# YosanoLoveButton.net
KiCad netlist of a schematic drawn in EAGLE
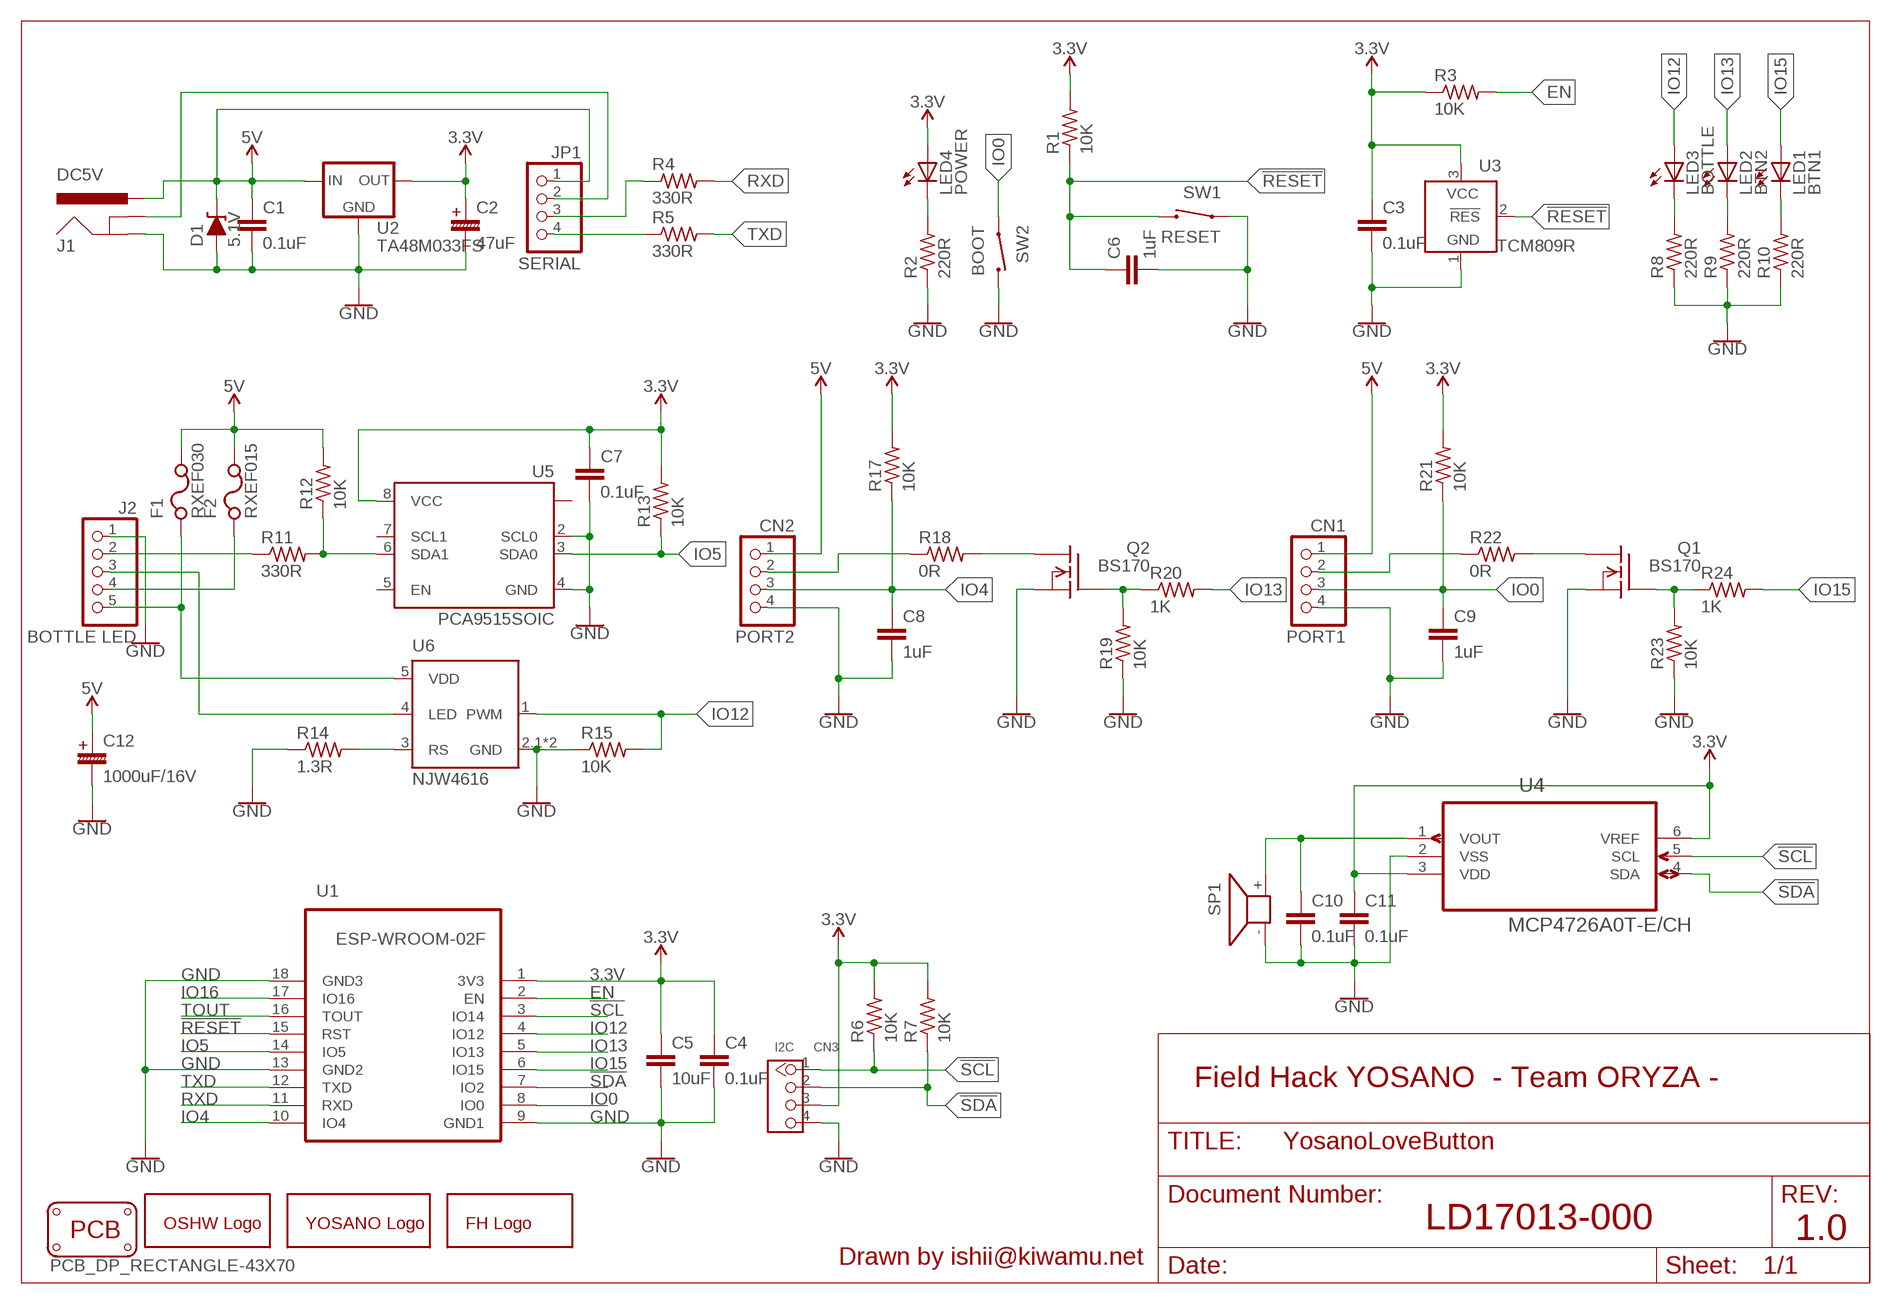
[diagram p0: schematic, sheet 1]

(export (version "E")
  (design (tool "Eeschema 10.0.6"))
  (components
    (comp (ref "C1")
      (value "0.1uF")
      (footprint "eagle-import:C5B2.5")
      (libsource (lib "eagle-import") (part "capacitor-wima_C5/2.5"))
    )
    (comp (ref "C2")
      (value "47uF")
      (footprint "eagle-import:E2,0-5")
      (libsource (lib "eagle-import") (part "C-PR-2,0X5"))
    )
    (comp (ref "C3")
      (value "0.1uF")
      (footprint "eagle-import:C5B2.5")
      (libsource (lib "eagle-import") (part "capacitor-wima_C5/2.5"))
    )
    (comp (ref "C4")
      (value "0.1uF")
      (footprint "eagle-import:C5B2.5")
      (libsource (lib "eagle-import") (part "capacitor-wima_C5/2.5"))
    )
    (comp (ref "C5")
      (value "10uF")
      (footprint "eagle-import:C5B2.5")
      (libsource (lib "eagle-import") (part "capacitor-wima_C5/2.5"))
    )
    (comp (ref "C6")
      (value "1uF")
      (footprint "eagle-import:C5B2.5")
      (libsource (lib "eagle-import") (part "capacitor-wima_C5/2.5"))
    )
    (comp (ref "C7")
      (value "0.1uF")
      (footprint "eagle-import:C5B2.5")
      (libsource (lib "eagle-import") (part "capacitor-wima_C5/2.5"))
    )
    (comp (ref "C8")
      (value "1uF")
      (footprint "eagle-import:C5B2.5")
      (libsource (lib "eagle-import") (part "capacitor-wima_C5/2.5"))
    )
    (comp (ref "C9")
      (value "1uF")
      (footprint "eagle-import:C5B2.5")
      (libsource (lib "eagle-import") (part "capacitor-wima_C5/2.5"))
    )
    (comp (ref "C10")
      (value "0.1uF")
      (footprint "eagle-import:C5B2.5")
      (fields (field (name "MF") "株式会社村田製作所(muRata)") (field (name "MPN") "RDER72E104K2K1H03B"))
      (libsource (lib "eagle-import") (part "C5/2.5"))
    )
    (comp (ref "C11")
      (value "0.1uF")
      (footprint "eagle-import:C5B2.5")
      (fields (field (name "MF") "株式会社村田製作所(muRata)") (field (name "MPN") "RDER72E104K2K1H03B"))
      (libsource (lib "eagle-import") (part "C5/2.5"))
    )
    (comp (ref "C12")
      (value "1000uF/16V")
      (footprint "eagle-import:E5,0-10")
      (libsource (lib "eagle-import") (part "C-PR-5,0X10"))
    )
    (comp (ref "CN1")
      (value "PORT1")
      (footprint "eagle-import:B4B-XH")
      (libsource (lib "eagle-import") (part "04-JST-XH-B4B-XH-A"))
    )
    (comp (ref "CN2")
      (value "PORT2")
      (footprint "eagle-import:B4B-XH")
      (libsource (lib "eagle-import") (part "04-JST-XH-B4B-XH-A"))
    )
    (comp (ref "CN3")
      (value "I2C")
      (footprint "eagle-import:HW4-2.0")
      (libsource (lib "eagle-import") (part "GROVE-CONNECTOR-DIP(4P-2.0)"))
    )
    (comp (ref "D1")
      (value "5.1V")
      (footprint "eagle-import:ZDIO-5-LD")
      (libsource (lib "eagle-import") (part "ZENER-DIODEZD-5LD"))
    )
    (comp (ref "F1")
      (value "RXEF030")
      (footprint "eagle-import:PTC-PTH")
      (libsource (lib "eagle-import") (part "PTCPTH"))
    )
    (comp (ref "F2")
      (value "RXEF015")
      (footprint "eagle-import:PTC-PTH")
      (libsource (lib "eagle-import") (part "PTCPTH"))
    )
    (comp (ref "GOLD_ORB_SM1")
      (value "OSHWLOGOLOGO5MM")
      (footprint "eagle-import:OSHW_5MM")
      (libsource (lib "eagle-import") (part "OSHWLOGOLOGO5MM"))
    )
    (comp (ref "J1")
      (value "DC5V")
      (footprint "eagle-import:POWER_JACK_PTH")
      (libsource (lib "eagle-import") (part "POWER_JACK"))
    )
    (comp (ref "J2")
      (value "BOTTLE LED")
      (footprint "eagle-import:MD-50SM")
      (fields (field (name "MF") "CUI") (field (name "MPN") "MD-50SM"))
      (libsource (lib "eagle-import") (part "MINIDIN-5P"))
    )
    (comp (ref "JP1")
      (value "SERIAL")
      (footprint "eagle-import:1X04")
      (libsource (lib "eagle-import") (part "PINHD-1X4"))
    )
    (comp (ref "LED1")
      (value "BTN1")
      (footprint "eagle-import:LED3MM")
      (libsource (lib "eagle-import") (part "LED3MM"))
    )
    (comp (ref "LED2")
      (value "BTN2")
      (footprint "eagle-import:LED3MM")
      (libsource (lib "eagle-import") (part "LED3MM"))
    )
    (comp (ref "LED3")
      (value "BOTTLE")
      (footprint "eagle-import:LED3MM")
      (libsource (lib "eagle-import") (part "LED3MM"))
    )
    (comp (ref "LED4")
      (value "POWER")
      (footprint "eagle-import:LED3MM")
      (libsource (lib "eagle-import") (part "LED3MM"))
    )
    (comp (ref "PCB1")
      (value "PCB_DP_RECTANGLE-43X70")
      (footprint "eagle-import:DP7043_V1")
      (libsource (lib "eagle-import") (part "PCB_DP_RECTANGLE-43X70"))
    )
    (comp (ref "Q1")
      (value "BS170")
      (footprint "eagle-import:TO92")
      (fields (field (name "MF") "FAIRCHILD"))
      (libsource (lib "eagle-import") (part "BS170"))
    )
    (comp (ref "Q2")
      (value "BS170")
      (footprint "eagle-import:TO92")
      (fields (field (name "MF") "FAIRCHILD"))
      (libsource (lib "eagle-import") (part "BS170"))
    )
    (comp (ref "R1")
      (value "10K")
      (footprint "eagle-import:0204_5")
      (libsource (lib "eagle-import") (part "R-US_0204/5"))
    )
    (comp (ref "R2")
      (value "220R")
      (footprint "eagle-import:0204_5")
      (libsource (lib "eagle-import") (part "R-US_0204/5"))
    )
    (comp (ref "R3")
      (value "10K")
      (footprint "eagle-import:0204_5")
      (libsource (lib "eagle-import") (part "R-US_0204/5"))
    )
    (comp (ref "R4")
      (value "330R")
      (footprint "eagle-import:0204_5")
      (libsource (lib "eagle-import") (part "R-US_0204/5"))
    )
    (comp (ref "R5")
      (value "330R")
      (footprint "eagle-import:0204_5")
      (libsource (lib "eagle-import") (part "R-US_0204/5"))
    )
    (comp (ref "R6")
      (value "10K")
      (footprint "eagle-import:0204_5")
      (libsource (lib "eagle-import") (part "R-US_0204/5"))
    )
    (comp (ref "R7")
      (value "10K")
      (footprint "eagle-import:0204_5")
      (libsource (lib "eagle-import") (part "R-US_0204/5"))
    )
    (comp (ref "R8")
      (value "220R")
      (footprint "eagle-import:0204_5")
      (libsource (lib "eagle-import") (part "R-US_0204/5"))
    )
    (comp (ref "R9")
      (value "220R")
      (footprint "eagle-import:0204_5")
      (libsource (lib "eagle-import") (part "R-US_0204/5"))
    )
    (comp (ref "R10")
      (value "220R")
      (footprint "eagle-import:0204_5")
      (libsource (lib "eagle-import") (part "R-US_0204/5"))
    )
    (comp (ref "R11")
      (value "330R")
      (footprint "eagle-import:0204_5")
      (libsource (lib "eagle-import") (part "R-US_0204/5"))
    )
    (comp (ref "R12")
      (value "10K")
      (footprint "eagle-import:0204_5")
      (libsource (lib "eagle-import") (part "R-US_0204/5"))
    )
    (comp (ref "R13")
      (value "10K")
      (footprint "eagle-import:0204_5")
      (libsource (lib "eagle-import") (part "R-US_0204/5"))
    )
    (comp (ref "R14")
      (value "1.3R")
      (footprint "eagle-import:0204_5")
      (libsource (lib "eagle-import") (part "R-US_0204/5"))
    )
    (comp (ref "R15")
      (value "10K")
      (footprint "eagle-import:0204_5")
      (libsource (lib "eagle-import") (part "R-US_0204/5"))
    )
    (comp (ref "R17")
      (value "10K")
      (footprint "eagle-import:0204_5")
      (libsource (lib "eagle-import") (part "R-US_0204/5"))
    )
    (comp (ref "R18")
      (value "0R")
      (footprint "eagle-import:0204_5")
      (libsource (lib "eagle-import") (part "R-US_0204/5"))
    )
    (comp (ref "R19")
      (value "10K")
      (footprint "eagle-import:0204_5")
      (libsource (lib "eagle-import") (part "R-US_0204/5"))
    )
    (comp (ref "R20")
      (value "1K")
      (footprint "eagle-import:0204_5")
      (libsource (lib "eagle-import") (part "R-US_0204/5"))
    )
    (comp (ref "R21")
      (value "10K")
      (footprint "eagle-import:0204_5")
      (libsource (lib "eagle-import") (part "R-US_0204/5"))
    )
    (comp (ref "R22")
      (value "0R")
      (footprint "eagle-import:0204_5")
      (libsource (lib "eagle-import") (part "R-US_0204/5"))
    )
    (comp (ref "R23")
      (value "10K")
      (footprint "eagle-import:0204_5")
      (libsource (lib "eagle-import") (part "R-US_0204/5"))
    )
    (comp (ref "R24")
      (value "1K")
      (footprint "eagle-import:0204_5")
      (libsource (lib "eagle-import") (part "R-US_0204/5"))
    )
    (comp (ref "SP1")
      (value "PKM13EPYH4000")
      (footprint "eagle-import:PKM13EPYH4000")
      (fields (field (name "MF") "muRata"))
      (libsource (lib "eagle-import") (part "PKM13EPYH4000"))
    )
    (comp (ref "SW1")
      (value "RESET")
      (footprint "eagle-import:TVBP06")
      (libsource (lib "eagle-import") (part "TVBP06"))
    )
    (comp (ref "SW2")
      (value "BOOT")
      (footprint "eagle-import:TVBP06")
      (libsource (lib "eagle-import") (part "TVBP06"))
    )
    (comp (ref "U$1")
      (value "YOSANOLOGO")
      (footprint "eagle-import:YOSANOCHO")
      (libsource (lib "eagle-import") (part "YOSANOLOGO"))
    )
    (comp (ref "U$2")
      (value "FHLOGO")
      (footprint "eagle-import:FIELDHACK-YOSANO")
      (libsource (lib "eagle-import") (part "FHLOGO"))
    )
    (comp (ref "U1")
      (value "ESP-WROOM-02F")
      (footprint "eagle-import:FRONT-FACE")
      (fields (field (name "MF") "Espressif") (field (name "MPN") "ESP-WROOM-02"))
      (libsource (lib "eagle-import") (part "ESP-WROOM-02F"))
    )
    (comp (ref "U2")
      (value "TA48M033FS")
      (footprint "eagle-import:HSIP3")
      (fields (field (name "MF") "株式会社東芝セミコンダクター社(TOSHIBA)") (field (name "MPN") "TA48M033F(S Q)"))
      (libsource (lib "eagle-import") (part "TA48MS033F"))
    )
    (comp (ref "U3")
      (value "TCM809R")
      (footprint "eagle-import:SOT23B-3")
      (fields (field (name "MF") "MICROCHIP") (field (name "MPN") "TCM809MENB713"))
      (libsource (lib "eagle-import") (part "TCM809"))
    )
    (comp (ref "U4")
      (value "MCP4726A0T-E/CH")
      (footprint "eagle-import:SOT95P270X145-6N")
      (fields (field (name "MF") "Microchip") (field (name "MPN") "MCP4725A0T-E/CH"))
      (libsource (lib "eagle-import") (part "MCP4726A0T-E/CH"))
    )
    (comp (ref "U5")
      (value "PCA9515SOIC")
      (footprint "eagle-import:SO08")
      (libsource (lib "eagle-import") (part "PCA9515SOIC"))
    )
    (comp (ref "U6")
      (value "NJW4616")
      (footprint "eagle-import:SOT-89-5")
      (libsource (lib "eagle-import") (part "NJW4616"))
    )
  )
  (nets
    (net (code "1") (name "/IO16") (class "Default")
      (node (ref "U1") (pin "17") (pinfunction "IO16_17") (pintype "bidirectional"))
    )
    (net (code "2") (name "/TOUT") (class "Default")
      (node (ref "U1") (pin "16") (pinfunction "TOUT_16") (pintype "bidirectional"))
    )
    (net (code "3") (name "/~{RESET}") (class "Default")
      (node (ref "C6") (pin "1") (pinfunction "1_1") (pintype "passive"))
      (node (ref "R1") (pin "1") (pinfunction "1_1") (pintype "passive"))
      (node (ref "SW1") (pin "2") (pinfunction "2_2") (pintype "passive"))
      (node (ref "U1") (pin "15") (pinfunction "RST_15") (pintype "bidirectional"))
      (node (ref "U3") (pin "2") (pinfunction "~{RES}_2") (pintype "output"))
    )
    (net (code "4") (name "/~{SCL}") (class "Default")
      (node (ref "CN3") (pin "1") (pinfunction "1_1") (pintype "bidirectional"))
      (node (ref "R6") (pin "1") (pinfunction "1_1") (pintype "passive"))
      (node (ref "U1") (pin "3") (pinfunction "IO14_3") (pintype "bidirectional"))
      (node (ref "U4") (pin "5") (pinfunction "SCL_5") (pintype "input"))
    )
    (net (code "5") (name "/~{SDA}") (class "Default")
      (node (ref "CN3") (pin "2") (pinfunction "2_2") (pintype "bidirectional"))
      (node (ref "R7") (pin "1") (pinfunction "1_1") (pintype "passive"))
      (node (ref "U1") (pin "7") (pinfunction "IO2_7") (pintype "bidirectional"))
      (node (ref "U4") (pin "4") (pinfunction "SDA_4") (pintype "bidirectional"))
    )
    (net (code "6") (name "3.3V") (class "Default")
      (node (ref "C11") (pin "1") (pinfunction "1_1") (pintype "passive"))
      (node (ref "C2") (pin "+") (pinfunction "+_+") (pintype "passive"))
      (node (ref "C3") (pin "1") (pinfunction "1_1") (pintype "passive"))
      (node (ref "C4") (pin "1") (pinfunction "1_1") (pintype "passive"))
      (node (ref "C5") (pin "1") (pinfunction "1_1") (pintype "passive"))
      (node (ref "C7") (pin "1") (pinfunction "1_1") (pintype "passive"))
      (node (ref "CN3") (pin "3") (pinfunction "3_3") (pintype "bidirectional"))
      (node (ref "LED4") (pin "A") (pinfunction "A_A") (pintype "passive"))
      (node (ref "R1") (pin "2") (pinfunction "2_2") (pintype "passive"))
      (node (ref "R13") (pin "2") (pinfunction "2_2") (pintype "passive"))
      (node (ref "R17") (pin "2") (pinfunction "2_2") (pintype "passive"))
      (node (ref "R21") (pin "2") (pinfunction "2_2") (pintype "passive"))
      (node (ref "R3") (pin "1") (pinfunction "1_1") (pintype "passive"))
      (node (ref "R6") (pin "2") (pinfunction "2_2") (pintype "passive"))
      (node (ref "R7") (pin "2") (pinfunction "2_2") (pintype "passive"))
      (node (ref "U1") (pin "1") (pinfunction "3V3_1") (pintype "power_in"))
      (node (ref "U2") (pin "P$2") (pinfunction "OUT_P$2") (pintype "passive"))
      (node (ref "U3") (pin "3") (pinfunction "VCC_3") (pintype "power_in"))
      (node (ref "U4") (pin "3") (pinfunction "VDD_3") (pintype "power_in"))
      (node (ref "U4") (pin "6") (pinfunction "VREF_6") (pintype "power_in"))
      (node (ref "U5") (pin "8") (pinfunction "VCC_8") (pintype "power_in"))
    )
    (net (code "7") (name "5V") (class "Default")
      (node (ref "C1") (pin "1") (pinfunction "1_1") (pintype "passive"))
      (node (ref "C12") (pin "+") (pinfunction "+_+") (pintype "passive"))
      (node (ref "CN1") (pin "1") (pinfunction "1_1") (pintype "passive"))
      (node (ref "CN2") (pin "1") (pinfunction "1_1") (pintype "passive"))
      (node (ref "D1") (pin "C") (pinfunction "C_C") (pintype "passive"))
      (node (ref "F1") (pin "2") (pinfunction "2_2") (pintype "bidirectional"))
      (node (ref "F2") (pin "2") (pinfunction "2_2") (pintype "bidirectional"))
      (node (ref "J1") (pin "PWR") (pinfunction "PWR_PWR") (pintype "bidirectional"))
      (node (ref "JP1") (pin "1") (pinfunction "1_1") (pintype "passive"))
      (node (ref "R12") (pin "2") (pinfunction "2_2") (pintype "passive"))
      (node (ref "U2") (pin "P$1") (pinfunction "IN_P$1") (pintype "input"))
    )
    (net (code "8") (name "EN") (class "Default")
      (node (ref "R3") (pin "2") (pinfunction "2_2") (pintype "passive"))
      (node (ref "U1") (pin "2") (pinfunction "EN_2") (pintype "bidirectional"))
    )
    (net (code "9") (name "GND") (class "Default")
      (node (ref "C1") (pin "2") (pinfunction "2_2") (pintype "passive"))
      (node (ref "C10") (pin "2") (pinfunction "2_2") (pintype "passive"))
      (node (ref "C11") (pin "2") (pinfunction "2_2") (pintype "passive"))
      (node (ref "C12") (pin "-") (pinfunction "-_-") (pintype "passive"))
      (node (ref "C2") (pin "-") (pinfunction "-_-") (pintype "passive"))
      (node (ref "C3") (pin "2") (pinfunction "2_2") (pintype "passive"))
      (node (ref "C4") (pin "2") (pinfunction "2_2") (pintype "passive"))
      (node (ref "C5") (pin "2") (pinfunction "2_2") (pintype "passive"))
      (node (ref "C6") (pin "2") (pinfunction "2_2") (pintype "passive"))
      (node (ref "C7") (pin "2") (pinfunction "2_2") (pintype "passive"))
      (node (ref "C8") (pin "2") (pinfunction "2_2") (pintype "passive"))
      (node (ref "C9") (pin "2") (pinfunction "2_2") (pintype "passive"))
      (node (ref "CN1") (pin "4") (pinfunction "4_4") (pintype "passive"))
      (node (ref "CN2") (pin "4") (pinfunction "4_4") (pintype "passive"))
      (node (ref "CN3") (pin "4") (pinfunction "4_4") (pintype "bidirectional"))
      (node (ref "D1") (pin "A") (pinfunction "A_A") (pintype "passive"))
      (node (ref "J1") (pin "GND") (pinfunction "GND_GND") (pintype "bidirectional"))
      (node (ref "J2") (pin "1") (pinfunction "1_1") (pintype "passive"))
      (node (ref "Q1") (pin "1") (pinfunction "S_1") (pintype "passive"))
      (node (ref "Q2") (pin "1") (pinfunction "S_1") (pintype "passive"))
      (node (ref "R10") (pin "1") (pinfunction "1_1") (pintype "passive"))
      (node (ref "R14") (pin "1") (pinfunction "1_1") (pintype "passive"))
      (node (ref "R15") (pin "1") (pinfunction "1_1") (pintype "passive"))
      (node (ref "R19") (pin "1") (pinfunction "1_1") (pintype "passive"))
      (node (ref "R2") (pin "1") (pinfunction "1_1") (pintype "passive"))
      (node (ref "R23") (pin "1") (pinfunction "1_1") (pintype "passive"))
      (node (ref "R8") (pin "1") (pinfunction "1_1") (pintype "passive"))
      (node (ref "R9") (pin "1") (pinfunction "1_1") (pintype "passive"))
      (node (ref "SP1") (pin "-") (pinfunction "2_-") (pintype "passive"))
      (node (ref "SW1") (pin "1") (pinfunction "1_1") (pintype "passive"))
      (node (ref "SW2") (pin "2") (pinfunction "2_2") (pintype "passive"))
      (node (ref "U1") (pin "13") (pinfunction "GND2_13") (pintype "power_in"))
      (node (ref "U1") (pin "18") (pinfunction "GND3_18") (pintype "power_in"))
      (node (ref "U1") (pin "9") (pinfunction "GND1_9") (pintype "power_in"))
      (node (ref "U2") (pin "P$3") (pinfunction "GND_P$3") (pintype "power_in"))
      (node (ref "U3") (pin "1") (pinfunction "GND_1") (pintype "power_in"))
      (node (ref "U4") (pin "2") (pinfunction "VSS_2") (pintype "power_in"))
      (node (ref "U5") (pin "2") (pinfunction "SCL0_2") (pintype "bidirectional"))
      (node (ref "U5") (pin "4") (pinfunction "GND_4") (pintype "power_in"))
      (node (ref "U6") (pin "2.1") (pinfunction "GND_2.1") (pintype "power_in"))
      (node (ref "U6") (pin "2.2") (pinfunction "GND_2.2") (pintype "power_in"))
    )
    (net (code "10") (name "IO0") (class "Default")
      (node (ref "C9") (pin "1") (pinfunction "1_1") (pintype "passive"))
      (node (ref "CN1") (pin "3") (pinfunction "3_3") (pintype "passive"))
      (node (ref "R21") (pin "1") (pinfunction "1_1") (pintype "passive"))
      (node (ref "SW2") (pin "1") (pinfunction "1_1") (pintype "passive"))
      (node (ref "U1") (pin "8") (pinfunction "IO0_8") (pintype "bidirectional"))
    )
    (net (code "11") (name "IO4") (class "Default")
      (node (ref "C8") (pin "1") (pinfunction "1_1") (pintype "passive"))
      (node (ref "CN2") (pin "3") (pinfunction "3_3") (pintype "passive"))
      (node (ref "R17") (pin "1") (pinfunction "1_1") (pintype "passive"))
      (node (ref "U1") (pin "10") (pinfunction "IO4_10") (pintype "bidirectional"))
    )
    (net (code "12") (name "IO5") (class "Default")
      (node (ref "R13") (pin "1") (pinfunction "1_1") (pintype "passive"))
      (node (ref "U1") (pin "14") (pinfunction "IO5_14") (pintype "open_collector"))
      (node (ref "U5") (pin "3") (pinfunction "SDA0_3") (pintype "bidirectional"))
    )
    (net (code "13") (name "IO12") (class "Default")
      (node (ref "LED3") (pin "A") (pinfunction "A_A") (pintype "passive"))
      (node (ref "R15") (pin "2") (pinfunction "2_2") (pintype "passive"))
      (node (ref "U1") (pin "4") (pinfunction "IO12_4") (pintype "bidirectional"))
      (node (ref "U6") (pin "1") (pinfunction "PWM_1") (pintype "input"))
    )
    (net (code "14") (name "IO13") (class "Default")
      (node (ref "LED2") (pin "A") (pinfunction "A_A") (pintype "passive"))
      (node (ref "R20") (pin "2") (pinfunction "2_2") (pintype "passive"))
      (node (ref "U1") (pin "5") (pinfunction "IO13_5") (pintype "bidirectional"))
    )
    (net (code "15") (name "IO15") (class "Default")
      (node (ref "LED1") (pin "A") (pinfunction "A_A") (pintype "passive"))
      (node (ref "R24") (pin "2") (pinfunction "2_2") (pintype "passive"))
      (node (ref "U1") (pin "6") (pinfunction "IO15_6") (pintype "bidirectional"))
    )
    (net (code "16") (name "Net-(CN1-Pad2)") (class "Default")
      (node (ref "CN1") (pin "2") (pinfunction "2_2") (pintype "passive"))
      (node (ref "R22") (pin "1") (pinfunction "1_1") (pintype "passive"))
    )
    (net (code "17") (name "Net-(CN2-Pad2)") (class "Default")
      (node (ref "CN2") (pin "2") (pinfunction "2_2") (pintype "passive"))
      (node (ref "R18") (pin "1") (pinfunction "1_1") (pintype "passive"))
    )
    (net (code "18") (name "Net-(F2-Pad1)") (class "Default")
      (node (ref "F2") (pin "1") (pinfunction "1_1") (pintype "bidirectional"))
      (node (ref "J2") (pin "4") (pinfunction "4_4") (pintype "passive"))
    )
    (net (code "19") (name "Net-(J1-PadGNDBREAK)") (class "Default")
      (node (ref "J1") (pin "GNDBREAK") (pinfunction "GNDBREAK_GNDBREAK") (pintype "bidirectional"))
      (node (ref "JP1") (pin "2") (pinfunction "2_2") (pintype "passive"))
    )
    (net (code "20") (name "Net-(J2-Pad2)") (class "Default")
      (node (ref "J2") (pin "2") (pinfunction "2_2") (pintype "passive"))
      (node (ref "R11") (pin "1") (pinfunction "1_1") (pintype "passive"))
    )
    (net (code "21") (name "Net-(JP1-Pad3)") (class "Default")
      (node (ref "JP1") (pin "3") (pinfunction "3_3") (pintype "passive"))
      (node (ref "R4") (pin "1") (pinfunction "1_1") (pintype "passive"))
    )
    (net (code "22") (name "Net-(JP1-Pad4)") (class "Default")
      (node (ref "JP1") (pin "4") (pinfunction "4_4") (pintype "passive"))
      (node (ref "R5") (pin "1") (pinfunction "1_1") (pintype "passive"))
    )
    (net (code "23") (name "Net-(LED1-C)") (class "Default")
      (node (ref "LED1") (pin "K") (pinfunction "C_K") (pintype "passive"))
      (node (ref "R10") (pin "2") (pinfunction "2_2") (pintype "passive"))
    )
    (net (code "24") (name "Net-(LED2-C)") (class "Default")
      (node (ref "LED2") (pin "K") (pinfunction "C_K") (pintype "passive"))
      (node (ref "R9") (pin "2") (pinfunction "2_2") (pintype "passive"))
    )
    (net (code "25") (name "Net-(LED3-C)") (class "Default")
      (node (ref "LED3") (pin "K") (pinfunction "C_K") (pintype "passive"))
      (node (ref "R8") (pin "2") (pinfunction "2_2") (pintype "passive"))
    )
    (net (code "26") (name "Net-(LED4-C)") (class "Default")
      (node (ref "LED4") (pin "K") (pinfunction "C_K") (pintype "passive"))
      (node (ref "R2") (pin "2") (pinfunction "2_2") (pintype "passive"))
    )
    (net (code "27") (name "Net-(Q1-D)") (class "Default")
      (node (ref "Q1") (pin "3") (pinfunction "D_3") (pintype "passive"))
      (node (ref "R22") (pin "2") (pinfunction "2_2") (pintype "passive"))
    )
    (net (code "28") (name "Net-(Q1-G)") (class "Default")
      (node (ref "Q1") (pin "2") (pinfunction "G_2") (pintype "passive"))
      (node (ref "R23") (pin "2") (pinfunction "2_2") (pintype "passive"))
      (node (ref "R24") (pin "1") (pinfunction "1_1") (pintype "passive"))
    )
    (net (code "29") (name "Net-(Q2-D)") (class "Default")
      (node (ref "Q2") (pin "3") (pinfunction "D_3") (pintype "passive"))
      (node (ref "R18") (pin "2") (pinfunction "2_2") (pintype "passive"))
    )
    (net (code "30") (name "Net-(Q2-G)") (class "Default")
      (node (ref "Q2") (pin "2") (pinfunction "G_2") (pintype "passive"))
      (node (ref "R19") (pin "2") (pinfunction "2_2") (pintype "passive"))
      (node (ref "R20") (pin "1") (pinfunction "1_1") (pintype "passive"))
    )
    (net (code "31") (name "Net-(SP1-1)") (class "Default")
      (node (ref "C10") (pin "1") (pinfunction "1_1") (pintype "passive"))
      (node (ref "SP1") (pin "+") (pinfunction "1_+") (pintype "passive"))
      (node (ref "U4") (pin "1") (pinfunction "VOUT_1") (pintype "output"))
    )
    (net (code "32") (name "Net-(U5-SDA1)") (class "Default")
      (node (ref "R11") (pin "2") (pinfunction "2_2") (pintype "passive"))
      (node (ref "R12") (pin "1") (pinfunction "1_1") (pintype "passive"))
      (node (ref "U5") (pin "6") (pinfunction "SDA1_6") (pintype "bidirectional"))
    )
    (net (code "33") (name "Net-(U6-LED)") (class "Default")
      (node (ref "J2") (pin "3") (pinfunction "3_3") (pintype "passive"))
      (node (ref "U6") (pin "4") (pinfunction "LED_4") (pintype "input"))
    )
    (net (code "34") (name "Net-(U6-RS)") (class "Default")
      (node (ref "R14") (pin "2") (pinfunction "2_2") (pintype "passive"))
      (node (ref "U6") (pin "3") (pinfunction "RS_3") (pintype "output"))
    )
    (net (code "35") (name "Net-(U6-VDD)") (class "Default")
      (node (ref "F1") (pin "1") (pinfunction "1_1") (pintype "bidirectional"))
      (node (ref "J2") (pin "5") (pinfunction "5_5") (pintype "passive"))
      (node (ref "U6") (pin "5") (pinfunction "VDD_5") (pintype "power_in"))
    )
    (net (code "36") (name "RXD") (class "Default")
      (node (ref "R4") (pin "2") (pinfunction "2_2") (pintype "passive"))
      (node (ref "U1") (pin "11") (pinfunction "RXD_11") (pintype "bidirectional"))
    )
    (net (code "37") (name "TXD") (class "Default")
      (node (ref "R5") (pin "2") (pinfunction "2_2") (pintype "passive"))
      (node (ref "U1") (pin "12") (pinfunction "TXD_12") (pintype "bidirectional"))
    )
    (net (code "38") (name "unconnected-(U5-EN-Pad5)") (class "Default")
      (node (ref "U5") (pin "5") (pinfunction "EN_5") (pintype "bidirectional"))
    )
    (net (code "39") (name "unconnected-(U5-N.C.-Pad1)") (class "Default")
      (node (ref "U5") (pin "1") (pinfunction "N.C._1") (pintype "no_connect"))
    )
    (net (code "40") (name "unconnected-(U5-SCL1-Pad7)") (class "Default")
      (node (ref "U5") (pin "7") (pinfunction "SCL1_7") (pintype "bidirectional"))
    )
  )
)
